# board.net
KiCad netlist of a schematic drawn in EAGLE
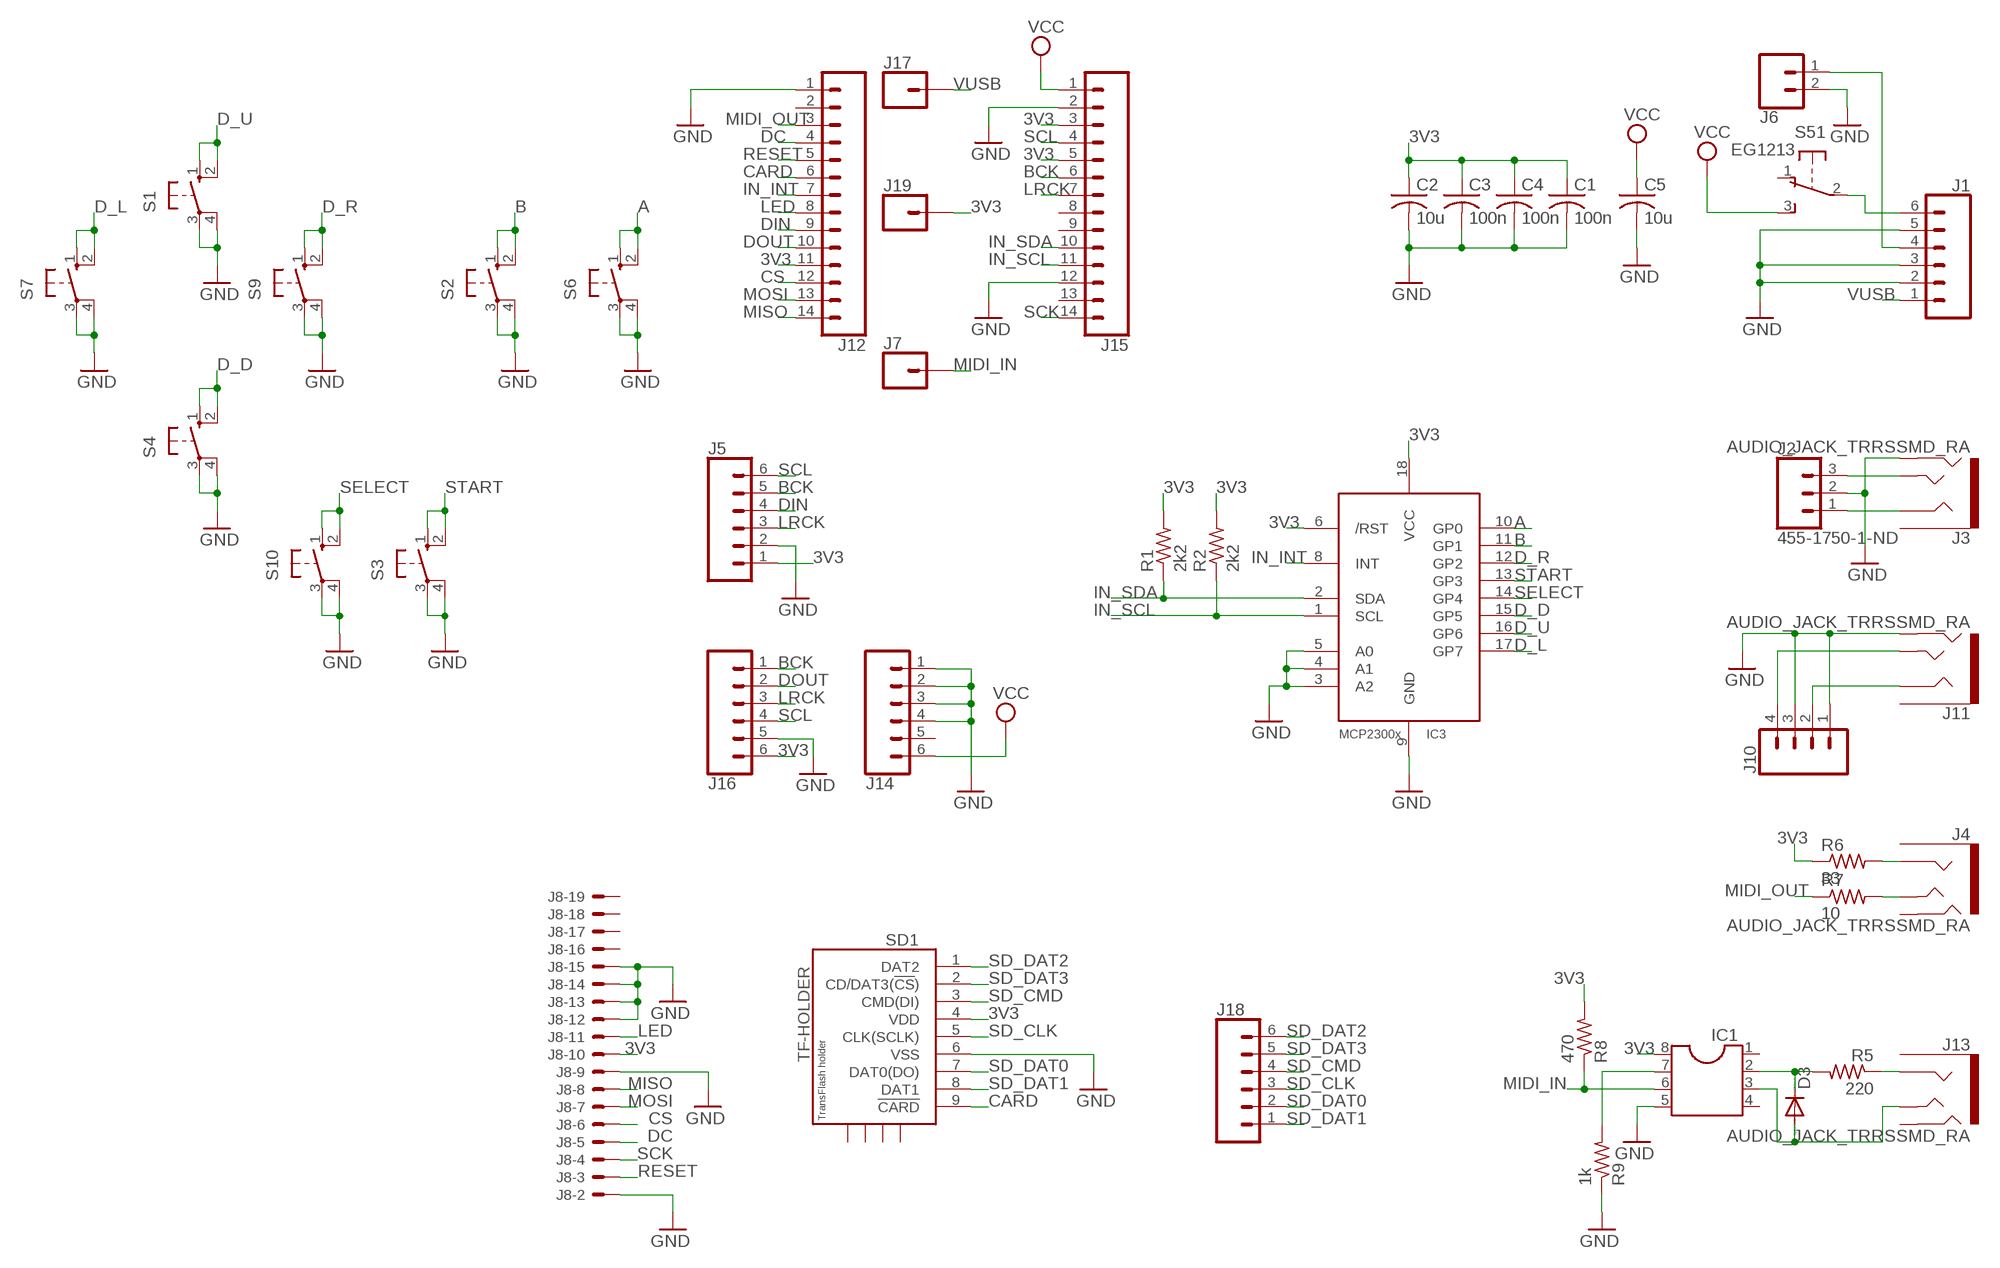
[diagram p0: schematic, sheet 1]

(export (version "E")
  (design (tool "Eeschema 10.0.6"))
  (components
    (comp (ref "C1")
      (value "100n")
      (footprint "eagle-import:C0805")
      (libsource (lib "eagle-import") (part "C-USC0805"))
    )
    (comp (ref "C2")
      (value "10u")
      (footprint "eagle-import:C0805")
      (libsource (lib "eagle-import") (part "C-USC0805"))
    )
    (comp (ref "C3")
      (value "100n")
      (footprint "eagle-import:C0805")
      (libsource (lib "eagle-import") (part "C-USC0805"))
    )
    (comp (ref "C4")
      (value "100n")
      (footprint "eagle-import:C0805")
      (libsource (lib "eagle-import") (part "C-USC0805"))
    )
    (comp (ref "C5")
      (value "10u")
      (footprint "eagle-import:C0805")
      (libsource (lib "eagle-import") (part "C-USC0805"))
    )
    (comp (ref "D3")
      (value "DIODE-MINIMELF")
      (footprint "eagle-import:MINIMELF")
      (libsource (lib "eagle-import") (part "DIODE-MINIMELF"))
    )
    (comp (ref "IC1")
      (value "DIL8")
      (footprint "eagle-import:DIL08")
      (libsource (lib "eagle-import") (part "DIL8"))
    )
    (comp (ref "IC3")
      (value "MCP23008/SO")
      (footprint "eagle-import:SO18W")
      (libsource (lib "eagle-import") (part "MCP23008/SO"))
    )
    (comp (ref "J1")
      (value "CONN_06SILK_FEMALE_PTH")
      (footprint "eagle-import:1X06")
      (libsource (lib "eagle-import") (part "CONN_06SILK_FEMALE_PTH"))
    )
    (comp (ref "J2")
      (value "455-1750-1-ND")
      (footprint "eagle-import:1X03")
      (libsource (lib "eagle-import") (part "CONN_03"))
    )
    (comp (ref "J3")
      (value "AUDIO_JACK_TRRSSMD_RA")
      (footprint "eagle-import:AUDIO_JACK_3.5MM_TRRS_SMD_RA")
      (libsource (lib "eagle-import") (part "AUDIO_JACK_TRRSSMD_RA"))
    )
    (comp (ref "J4")
      (value "AUDIO_JACK_TRRSSMD_RA")
      (footprint "eagle-import:AUDIO_JACK_3.5MM_TRRS_SMD_RA")
      (libsource (lib "eagle-import") (part "AUDIO_JACK_TRRSSMD_RA"))
    )
    (comp (ref "J5")
      (value "CONN_06SILK_FEMALE_PTH")
      (footprint "eagle-import:1X06")
      (libsource (lib "eagle-import") (part "CONN_06SILK_FEMALE_PTH"))
    )
    (comp (ref "J6")
      (value "CONN_02")
      (footprint "eagle-import:1X02")
      (libsource (lib "eagle-import") (part "CONN_02"))
    )
    (comp (ref "J7")
      (value "CONN_01")
      (footprint "eagle-import:1X01")
      (libsource (lib "eagle-import") (part "CONN_01"))
    )
    (comp (ref "J8")
      (value "XF2E-2015-1")
      (footprint "eagle-import:XF2E-2015-1")
      (libsource (lib "eagle-import") (part "XF2-20?15-1E"))
    )
    (comp (ref "J10")
      (value "CONN_04")
      (footprint "eagle-import:1X04")
      (libsource (lib "eagle-import") (part "CONN_04"))
    )
    (comp (ref "J11")
      (value "AUDIO_JACK_TRRSSMD_RA")
      (footprint "eagle-import:AUDIO_JACK_3.5MM_TRRS_SMD_RA")
      (libsource (lib "eagle-import") (part "AUDIO_JACK_TRRSSMD_RA"))
    )
    (comp (ref "J12")
      (value "CONN_14")
      (footprint "eagle-import:1X14")
      (libsource (lib "eagle-import") (part "CONN_14"))
    )
    (comp (ref "J13")
      (value "AUDIO_JACK_TRRSSMD_RA")
      (footprint "eagle-import:AUDIO_JACK_3.5MM_TRRS_SMD_RA")
      (libsource (lib "eagle-import") (part "AUDIO_JACK_TRRSSMD_RA"))
    )
    (comp (ref "J14")
      (value "CONN_06SILK_FEMALE_PTH")
      (footprint "eagle-import:1X06")
      (libsource (lib "eagle-import") (part "CONN_06SILK_FEMALE_PTH"))
    )
    (comp (ref "J15")
      (value "CONN_14")
      (footprint "eagle-import:1X14")
      (libsource (lib "eagle-import") (part "CONN_14"))
    )
    (comp (ref "J16")
      (value "CONN_06SILK_FEMALE_PTH")
      (footprint "eagle-import:1X06")
      (libsource (lib "eagle-import") (part "CONN_06SILK_FEMALE_PTH"))
    )
    (comp (ref "J17")
      (value "CONN_01")
      (footprint "eagle-import:1X01")
      (libsource (lib "eagle-import") (part "CONN_01"))
    )
    (comp (ref "J18")
      (value "CONN_06SILK_FEMALE_PTH")
      (footprint "eagle-import:1X06")
      (libsource (lib "eagle-import") (part "CONN_06SILK_FEMALE_PTH"))
    )
    (comp (ref "J19")
      (value "CONN_01")
      (footprint "eagle-import:1X01")
      (libsource (lib "eagle-import") (part "CONN_01"))
    )
    (comp (ref "R1")
      (value "2k2")
      (footprint "eagle-import:R0805")
      (libsource (lib "eagle-import") (part "R-US_R0805"))
    )
    (comp (ref "R2")
      (value "2k2")
      (footprint "eagle-import:R0805")
      (libsource (lib "eagle-import") (part "R-US_R0805"))
    )
    (comp (ref "R5")
      (value "220")
      (footprint "eagle-import:R0805")
      (libsource (lib "eagle-import") (part "R-US_R0805"))
    )
    (comp (ref "R6")
      (value "33")
      (footprint "eagle-import:R0805")
      (libsource (lib "eagle-import") (part "R-US_R0805"))
    )
    (comp (ref "R7")
      (value "10")
      (footprint "eagle-import:R0805")
      (libsource (lib "eagle-import") (part "R-US_R0805"))
    )
    (comp (ref "R8")
      (value "470")
      (footprint "eagle-import:R0805")
      (libsource (lib "eagle-import") (part "R-US_R0805"))
    )
    (comp (ref "R9")
      (value "1k")
      (footprint "eagle-import:R0805")
      (libsource (lib "eagle-import") (part "R-US_R0805"))
    )
    (comp (ref "S1")
      (value "10-XX")
      (footprint "eagle-import:B3F-10XX")
      (fields (field (name "MPN") "B3F-1000"))
      (libsource (lib "eagle-import") (part "10-XX"))
    )
    (comp (ref "S2")
      (value "10-XX")
      (footprint "eagle-import:B3F-10XX")
      (fields (field (name "MPN") "B3F-1000"))
      (libsource (lib "eagle-import") (part "10-XX"))
    )
    (comp (ref "S3")
      (value "10-XX")
      (footprint "eagle-import:B3F-10XX")
      (fields (field (name "MPN") "B3F-1000"))
      (libsource (lib "eagle-import") (part "10-XX"))
    )
    (comp (ref "S4")
      (value "10-XX")
      (footprint "eagle-import:B3F-10XX")
      (fields (field (name "MPN") "B3F-1000"))
      (libsource (lib "eagle-import") (part "10-XX"))
    )
    (comp (ref "S5")
      (value "EG1213")
      (footprint "eagle-import:EG1213")
      (libsource (lib "eagle-import") (part "EG1213"))
    )
    (comp (ref "S6")
      (value "10-XX")
      (footprint "eagle-import:B3F-10XX")
      (fields (field (name "MPN") "B3F-1000"))
      (libsource (lib "eagle-import") (part "10-XX"))
    )
    (comp (ref "S7")
      (value "10-XX")
      (footprint "eagle-import:B3F-10XX")
      (fields (field (name "MPN") "B3F-1000"))
      (libsource (lib "eagle-import") (part "10-XX"))
    )
    (comp (ref "S9")
      (value "10-XX")
      (footprint "eagle-import:B3F-10XX")
      (fields (field (name "MPN") "B3F-1000"))
      (libsource (lib "eagle-import") (part "10-XX"))
    )
    (comp (ref "S10")
      (value "10-XX")
      (footprint "eagle-import:B3F-10XX")
      (fields (field (name "MPN") "B3F-1000"))
      (libsource (lib "eagle-import") (part "10-XX"))
    )
    (comp (ref "SD1")
      (value "TF-HOLDER")
      (footprint "eagle-import:TF-PULL")
      (libsource (lib "eagle-import") (part "TF-HOLDER"))
    )
  )
  (nets
    (net (code "1") (name "/3V3") (class "Default")
      (node (ref "C1") (pin "1") (pinfunction "1_1") (pintype "passive"))
      (node (ref "C2") (pin "1") (pinfunction "1_1") (pintype "passive"))
      (node (ref "C3") (pin "1") (pinfunction "1_1") (pintype "passive"))
      (node (ref "C4") (pin "1") (pinfunction "1_1") (pintype "passive"))
      (node (ref "IC1") (pin "8") (pinfunction "8_8") (pintype "passive"))
      (node (ref "IC3") (pin "18") (pinfunction "VCC_18") (pintype "power_in"))
      (node (ref "IC3") (pin "6") (pinfunction "/RST_6") (pintype "input"))
      (node (ref "J12") (pin "11") (pinfunction "11_11") (pintype "passive"))
      (node (ref "J15") (pin "3") (pinfunction "3_3") (pintype "passive"))
      (node (ref "J15") (pin "5") (pinfunction "5_5") (pintype "passive"))
      (node (ref "J16") (pin "6") (pinfunction "6_6") (pintype "passive"))
      (node (ref "J19") (pin "1") (pinfunction "1_1") (pintype "passive"))
      (node (ref "J5") (pin "1") (pinfunction "1_1") (pintype "passive"))
      (node (ref "J8") (pin "10") (pinfunction "MS_10") (pintype "passive"))
      (node (ref "R1") (pin "2") (pinfunction "2_2") (pintype "passive"))
      (node (ref "R2") (pin "2") (pinfunction "2_2") (pintype "passive"))
      (node (ref "R6") (pin "1") (pinfunction "1_1") (pintype "passive"))
      (node (ref "R8") (pin "2") (pinfunction "2_2") (pintype "passive"))
      (node (ref "SD1") (pin "4") (pinfunction "VDD_4") (pintype "power_in"))
    )
    (net (code "2") (name "/A") (class "Default")
      (node (ref "IC3") (pin "10") (pinfunction "GP0_10") (pintype "bidirectional"))
      (node (ref "S6") (pin "1") (pinfunction "S_1") (pintype "passive"))
      (node (ref "S6") (pin "2") (pinfunction "S1_2") (pintype "passive"))
    )
    (net (code "3") (name "/B") (class "Default")
      (node (ref "IC3") (pin "11") (pinfunction "GP1_11") (pintype "bidirectional"))
      (node (ref "S2") (pin "1") (pinfunction "S_1") (pintype "passive"))
      (node (ref "S2") (pin "2") (pinfunction "S1_2") (pintype "passive"))
    )
    (net (code "4") (name "/BCK") (class "Default")
      (node (ref "J15") (pin "6") (pinfunction "6_6") (pintype "passive"))
      (node (ref "J16") (pin "1") (pinfunction "1_1") (pintype "passive"))
      (node (ref "J5") (pin "5") (pinfunction "5_5") (pintype "passive"))
    )
    (net (code "5") (name "/CARD") (class "Default")
      (node (ref "J12") (pin "6") (pinfunction "6_6") (pintype "passive"))
      (node (ref "SD1") (pin "9") (pinfunction "~{CARD}_9") (pintype "passive"))
    )
    (net (code "6") (name "/CS") (class "Default")
      (node (ref "J12") (pin "12") (pinfunction "12_12") (pintype "passive"))
      (node (ref "J8") (pin "6") (pinfunction "MS_6") (pintype "passive"))
    )
    (net (code "7") (name "/DC") (class "Default")
      (node (ref "J12") (pin "4") (pinfunction "4_4") (pintype "passive"))
      (node (ref "J8") (pin "5") (pinfunction "MS_5") (pintype "passive"))
    )
    (net (code "8") (name "/DIN") (class "Default")
      (node (ref "J12") (pin "9") (pinfunction "9_9") (pintype "passive"))
      (node (ref "J5") (pin "4") (pinfunction "4_4") (pintype "passive"))
    )
    (net (code "9") (name "/DOUT") (class "Default")
      (node (ref "J12") (pin "10") (pinfunction "10_10") (pintype "passive"))
      (node (ref "J16") (pin "2") (pinfunction "2_2") (pintype "passive"))
    )
    (net (code "10") (name "/D_D") (class "Default")
      (node (ref "IC3") (pin "15") (pinfunction "GP5_15") (pintype "bidirectional"))
      (node (ref "S4") (pin "1") (pinfunction "S_1") (pintype "passive"))
      (node (ref "S4") (pin "2") (pinfunction "S1_2") (pintype "passive"))
    )
    (net (code "11") (name "/D_L") (class "Default")
      (node (ref "IC3") (pin "17") (pinfunction "GP7_17") (pintype "bidirectional"))
      (node (ref "S7") (pin "1") (pinfunction "S_1") (pintype "passive"))
      (node (ref "S7") (pin "2") (pinfunction "S1_2") (pintype "passive"))
    )
    (net (code "12") (name "/D_R") (class "Default")
      (node (ref "IC3") (pin "12") (pinfunction "GP2_12") (pintype "bidirectional"))
      (node (ref "S9") (pin "1") (pinfunction "S_1") (pintype "passive"))
      (node (ref "S9") (pin "2") (pinfunction "S1_2") (pintype "passive"))
    )
    (net (code "13") (name "/D_U") (class "Default")
      (node (ref "IC3") (pin "16") (pinfunction "GP6_16") (pintype "bidirectional"))
      (node (ref "S1") (pin "1") (pinfunction "S_1") (pintype "passive"))
      (node (ref "S1") (pin "2") (pinfunction "S1_2") (pintype "passive"))
    )
    (net (code "14") (name "/IN_INT") (class "Default")
      (node (ref "IC3") (pin "8") (pinfunction "INT_8") (pintype "output"))
      (node (ref "J12") (pin "7") (pinfunction "7_7") (pintype "passive"))
    )
    (net (code "15") (name "/IN_SCL") (class "Default")
      (node (ref "IC3") (pin "1") (pinfunction "SCL_1") (pintype "bidirectional"))
      (node (ref "J15") (pin "11") (pinfunction "11_11") (pintype "passive"))
      (node (ref "R2") (pin "1") (pinfunction "1_1") (pintype "passive"))
    )
    (net (code "16") (name "/IN_SDA") (class "Default")
      (node (ref "IC3") (pin "2") (pinfunction "SDA_2") (pintype "bidirectional"))
      (node (ref "J15") (pin "10") (pinfunction "10_10") (pintype "passive"))
      (node (ref "R1") (pin "1") (pinfunction "1_1") (pintype "passive"))
    )
    (net (code "17") (name "/LED") (class "Default")
      (node (ref "J12") (pin "8") (pinfunction "8_8") (pintype "passive"))
      (node (ref "J8") (pin "11") (pinfunction "MS_11") (pintype "passive"))
    )
    (net (code "18") (name "/LRCK") (class "Default")
      (node (ref "J15") (pin "7") (pinfunction "7_7") (pintype "passive"))
      (node (ref "J16") (pin "3") (pinfunction "3_3") (pintype "passive"))
      (node (ref "J5") (pin "3") (pinfunction "3_3") (pintype "passive"))
    )
    (net (code "19") (name "/MIDI_IN") (class "Default")
      (node (ref "IC1") (pin "6") (pinfunction "6_6") (pintype "passive"))
      (node (ref "J7") (pin "1") (pinfunction "1_1") (pintype "passive"))
      (node (ref "R8") (pin "1") (pinfunction "1_1") (pintype "passive"))
    )
    (net (code "20") (name "/MIDI_OUT") (class "Default")
      (node (ref "J12") (pin "3") (pinfunction "3_3") (pintype "passive"))
      (node (ref "R7") (pin "1") (pinfunction "1_1") (pintype "passive"))
    )
    (net (code "21") (name "/MISO") (class "Default")
      (node (ref "J12") (pin "14") (pinfunction "14_14") (pintype "passive"))
      (node (ref "J8") (pin "8") (pinfunction "MS_8") (pintype "passive"))
    )
    (net (code "22") (name "/MOSI") (class "Default")
      (node (ref "J12") (pin "13") (pinfunction "13_13") (pintype "passive"))
      (node (ref "J8") (pin "7") (pinfunction "MS_7") (pintype "passive"))
    )
    (net (code "23") (name "/RESET") (class "Default")
      (node (ref "J12") (pin "5") (pinfunction "5_5") (pintype "passive"))
      (node (ref "J8") (pin "3") (pinfunction "MS_3") (pintype "passive"))
    )
    (net (code "24") (name "/SCK") (class "Default")
      (node (ref "J15") (pin "14") (pinfunction "14_14") (pintype "passive"))
      (node (ref "J8") (pin "4") (pinfunction "MS_4") (pintype "passive"))
    )
    (net (code "25") (name "/SCL") (class "Default")
      (node (ref "J15") (pin "4") (pinfunction "4_4") (pintype "passive"))
      (node (ref "J16") (pin "4") (pinfunction "4_4") (pintype "passive"))
      (node (ref "J5") (pin "6") (pinfunction "6_6") (pintype "passive"))
    )
    (net (code "26") (name "/SD_CLK") (class "Default")
      (node (ref "J18") (pin "3") (pinfunction "3_3") (pintype "passive"))
      (node (ref "SD1") (pin "5") (pinfunction "CLK(SCLK)_5") (pintype "input"))
    )
    (net (code "27") (name "/SD_CMD") (class "Default")
      (node (ref "J18") (pin "4") (pinfunction "4_4") (pintype "passive"))
      (node (ref "SD1") (pin "3") (pinfunction "CMD(DI)_3") (pintype "bidirectional"))
    )
    (net (code "28") (name "/SD_DAT0") (class "Default")
      (node (ref "J18") (pin "2") (pinfunction "2_2") (pintype "passive"))
      (node (ref "SD1") (pin "7") (pinfunction "DAT0(DO)_7") (pintype "bidirectional"))
    )
    (net (code "29") (name "/SD_DAT1") (class "Default")
      (node (ref "J18") (pin "1") (pinfunction "1_1") (pintype "passive"))
      (node (ref "SD1") (pin "8") (pinfunction "DAT1_8") (pintype "bidirectional"))
    )
    (net (code "30") (name "/SD_DAT2") (class "Default")
      (node (ref "J18") (pin "6") (pinfunction "6_6") (pintype "passive"))
      (node (ref "SD1") (pin "1") (pinfunction "DAT2_1") (pintype "bidirectional"))
    )
    (net (code "31") (name "/SD_DAT3") (class "Default")
      (node (ref "J18") (pin "5") (pinfunction "5_5") (pintype "passive"))
      (node (ref "SD1") (pin "2") (pinfunction "CD/DAT3(~{CS})_2") (pintype "bidirectional"))
    )
    (net (code "32") (name "/SELECT") (class "Default")
      (node (ref "IC3") (pin "14") (pinfunction "GP4_14") (pintype "bidirectional"))
      (node (ref "S10") (pin "1") (pinfunction "S_1") (pintype "passive"))
      (node (ref "S10") (pin "2") (pinfunction "S1_2") (pintype "passive"))
    )
    (net (code "33") (name "/START") (class "Default")
      (node (ref "IC3") (pin "13") (pinfunction "GP3_13") (pintype "bidirectional"))
      (node (ref "S3") (pin "1") (pinfunction "S_1") (pintype "passive"))
      (node (ref "S3") (pin "2") (pinfunction "S1_2") (pintype "passive"))
    )
    (net (code "34") (name "/VUSB") (class "Default")
      (node (ref "J1") (pin "1") (pinfunction "1_1") (pintype "passive"))
      (node (ref "J17") (pin "1") (pinfunction "1_1") (pintype "passive"))
    )
    (net (code "35") (name "GND") (class "Default")
      (node (ref "C1") (pin "2") (pinfunction "2_2") (pintype "passive"))
      (node (ref "C2") (pin "2") (pinfunction "2_2") (pintype "passive"))
      (node (ref "C3") (pin "2") (pinfunction "2_2") (pintype "passive"))
      (node (ref "C4") (pin "2") (pinfunction "2_2") (pintype "passive"))
      (node (ref "C5") (pin "2") (pinfunction "2_2") (pintype "passive"))
      (node (ref "IC1") (pin "5") (pinfunction "5_5") (pintype "passive"))
      (node (ref "IC3") (pin "3") (pinfunction "A2_3") (pintype "input"))
      (node (ref "IC3") (pin "4") (pinfunction "A1_4") (pintype "input"))
      (node (ref "IC3") (pin "5") (pinfunction "A0_5") (pintype "input"))
      (node (ref "IC3") (pin "9") (pinfunction "GND_9") (pintype "power_in"))
      (node (ref "J1") (pin "2") (pinfunction "2_2") (pintype "passive"))
      (node (ref "J1") (pin "3") (pinfunction "3_3") (pintype "passive"))
      (node (ref "J1") (pin "5") (pinfunction "5_5") (pintype "passive"))
      (node (ref "J10") (pin "1") (pinfunction "1_1") (pintype "passive"))
      (node (ref "J10") (pin "3") (pinfunction "3_3") (pintype "passive"))
      (node (ref "J11") (pin "RING2") (pinfunction "RING2_RING2") (pintype "bidirectional"))
      (node (ref "J12") (pin "1") (pinfunction "1_1") (pintype "passive"))
      (node (ref "J14") (pin "1") (pinfunction "1_1") (pintype "passive"))
      (node (ref "J14") (pin "2") (pinfunction "2_2") (pintype "passive"))
      (node (ref "J14") (pin "3") (pinfunction "3_3") (pintype "passive"))
      (node (ref "J14") (pin "4") (pinfunction "4_4") (pintype "passive"))
      (node (ref "J15") (pin "12") (pinfunction "12_12") (pintype "passive"))
      (node (ref "J15") (pin "2") (pinfunction "2_2") (pintype "passive"))
      (node (ref "J16") (pin "5") (pinfunction "5_5") (pintype "passive"))
      (node (ref "J2") (pin "2") (pinfunction "2_2") (pintype "passive"))
      (node (ref "J3") (pin "RING2") (pinfunction "RING2_RING2") (pintype "bidirectional"))
      (node (ref "J5") (pin "2") (pinfunction "2_2") (pintype "passive"))
      (node (ref "J6") (pin "2") (pinfunction "2_2") (pintype "passive"))
      (node (ref "J8") (pin "12") (pinfunction "MS_12") (pintype "passive"))
      (node (ref "J8") (pin "13") (pinfunction "MS_13") (pintype "passive"))
      (node (ref "J8") (pin "14") (pinfunction "MS_14") (pintype "passive"))
      (node (ref "J8") (pin "15") (pinfunction "MS_15") (pintype "passive"))
      (node (ref "J8") (pin "2") (pinfunction "MS_2") (pintype "passive"))
      (node (ref "J8") (pin "9") (pinfunction "MS_9") (pintype "passive"))
      (node (ref "R9") (pin "1") (pinfunction "1_1") (pintype "passive"))
      (node (ref "S1") (pin "3") (pinfunction "P_3") (pintype "passive"))
      (node (ref "S1") (pin "4") (pinfunction "P1_4") (pintype "passive"))
      (node (ref "S10") (pin "3") (pinfunction "P_3") (pintype "passive"))
      (node (ref "S10") (pin "4") (pinfunction "P1_4") (pintype "passive"))
      (node (ref "S2") (pin "3") (pinfunction "P_3") (pintype "passive"))
      (node (ref "S2") (pin "4") (pinfunction "P1_4") (pintype "passive"))
      (node (ref "S3") (pin "3") (pinfunction "P_3") (pintype "passive"))
      (node (ref "S3") (pin "4") (pinfunction "P1_4") (pintype "passive"))
      (node (ref "S4") (pin "3") (pinfunction "P_3") (pintype "passive"))
      (node (ref "S4") (pin "4") (pinfunction "P1_4") (pintype "passive"))
      (node (ref "S6") (pin "3") (pinfunction "P_3") (pintype "passive"))
      (node (ref "S6") (pin "4") (pinfunction "P1_4") (pintype "passive"))
      (node (ref "S7") (pin "3") (pinfunction "P_3") (pintype "passive"))
      (node (ref "S7") (pin "4") (pinfunction "P1_4") (pintype "passive"))
      (node (ref "S9") (pin "3") (pinfunction "P_3") (pintype "passive"))
      (node (ref "S9") (pin "4") (pinfunction "P1_4") (pintype "passive"))
      (node (ref "SD1") (pin "6") (pinfunction "VSS_6") (pintype "power_in"))
    )
    (net (code "36") (name "Net-(D3-PadA)") (class "Default")
      (node (ref "D3") (pin "A") (pinfunction "A_A") (pintype "passive"))
      (node (ref "IC1") (pin "3") (pinfunction "3_3") (pintype "passive"))
      (node (ref "J13") (pin "TIP") (pinfunction "TIP_TIP") (pintype "bidirectional"))
    )
    (net (code "37") (name "Net-(D3-PadC)") (class "Default")
      (node (ref "D3") (pin "C") (pinfunction "C_C") (pintype "passive"))
      (node (ref "IC1") (pin "2") (pinfunction "2_2") (pintype "passive"))
      (node (ref "R5") (pin "2") (pinfunction "2_2") (pintype "passive"))
    )
    (net (code "38") (name "Net-(IC1-Pad7)") (class "Default")
      (node (ref "IC1") (pin "7") (pinfunction "7_7") (pintype "passive"))
      (node (ref "R9") (pin "2") (pinfunction "2_2") (pintype "passive"))
    )
    (net (code "39") (name "Net-(J1-Pad4)") (class "Default")
      (node (ref "J1") (pin "4") (pinfunction "4_4") (pintype "passive"))
      (node (ref "J6") (pin "1") (pinfunction "1_1") (pintype "passive"))
    )
    (net (code "40") (name "Net-(J2-Pad1)") (class "Default")
      (node (ref "J2") (pin "1") (pinfunction "1_1") (pintype "passive"))
      (node (ref "J3") (pin "RING1") (pinfunction "RING1_RING1") (pintype "bidirectional"))
    )
    (net (code "41") (name "Net-(J2-Pad3)") (class "Default")
      (node (ref "J2") (pin "3") (pinfunction "3_3") (pintype "passive"))
      (node (ref "J3") (pin "TIP") (pinfunction "TIP_TIP") (pintype "bidirectional"))
    )
    (net (code "42") (name "Net-(J4-PadRING1)") (class "Default")
      (node (ref "J4") (pin "RING1") (pinfunction "RING1_RING1") (pintype "bidirectional"))
      (node (ref "R6") (pin "2") (pinfunction "2_2") (pintype "passive"))
    )
    (net (code "43") (name "Net-(J4-PadTIP)") (class "Default")
      (node (ref "J4") (pin "TIP") (pinfunction "TIP_TIP") (pintype "bidirectional"))
      (node (ref "R7") (pin "2") (pinfunction "2_2") (pintype "passive"))
    )
    (net (code "44") (name "Net-(J10-Pad2)") (class "Default")
      (node (ref "J10") (pin "2") (pinfunction "2_2") (pintype "passive"))
      (node (ref "J11") (pin "RING1") (pinfunction "RING1_RING1") (pintype "bidirectional"))
    )
    (net (code "45") (name "Net-(J10-Pad4)") (class "Default")
      (node (ref "J10") (pin "4") (pinfunction "4_4") (pintype "passive"))
      (node (ref "J11") (pin "TIP") (pinfunction "TIP_TIP") (pintype "bidirectional"))
    )
    (net (code "46") (name "Net-(J13-PadRING1)") (class "Default")
      (node (ref "J13") (pin "RING1") (pinfunction "RING1_RING1") (pintype "bidirectional"))
      (node (ref "R5") (pin "1") (pinfunction "1_1") (pintype "passive"))
    )
    (net (code "47") (name "Net-(S5A-P)") (class "Default")
      (node (ref "J1") (pin "6") (pinfunction "6_6") (pintype "passive"))
      (node (ref "S5") (pin "2") (pinfunction "P_2") (pintype "passive"))
    )
    (net (code "48") (name "VCC") (class "Default")
      (node (ref "C5") (pin "1") (pinfunction "1_1") (pintype "passive"))
      (node (ref "J14") (pin "6") (pinfunction "6_6") (pintype "passive"))
      (node (ref "J15") (pin "1") (pinfunction "1_1") (pintype "passive"))
      (node (ref "S5") (pin "3") (pinfunction "S_3") (pintype "passive"))
    )
    (net (code "49") (name "unconnected-(IC1-Pad1)") (class "Default")
      (node (ref "IC1") (pin "1") (pinfunction "1_1") (pintype "passive"))
    )
    (net (code "50") (name "unconnected-(IC1-Pad4)") (class "Default")
      (node (ref "IC1") (pin "4") (pinfunction "4_4") (pintype "passive"))
    )
    (net (code "51") (name "unconnected-(J3-PadEARTH)") (class "Default")
      (node (ref "J3") (pin "EARTH") (pinfunction "EARTH_EARTH") (pintype "bidirectional"))
    )
    (net (code "52") (name "unconnected-(J4-PadEARTH)") (class "Default")
      (node (ref "J4") (pin "EARTH") (pinfunction "EARTH_EARTH") (pintype "bidirectional"))
    )
    (net (code "53") (name "unconnected-(J4-PadRING2)") (class "Default")
      (node (ref "J4") (pin "RING2") (pinfunction "RING2_RING2") (pintype "bidirectional"))
    )
    (net (code "54") (name "unconnected-(J8G-MS-Pad16)") (class "Default")
      (node (ref "J8") (pin "16") (pinfunction "MS_16") (pintype "passive"))
    )
    (net (code "55") (name "unconnected-(J8H-MS-Pad17)") (class "Default")
      (node (ref "J8") (pin "17") (pinfunction "MS_17") (pintype "passive"))
    )
    (net (code "56") (name "unconnected-(J8I-MS-Pad18)") (class "Default")
      (node (ref "J8") (pin "18") (pinfunction "MS_18") (pintype "passive"))
    )
    (net (code "57") (name "unconnected-(J8J-MS-Pad19)") (class "Default")
      (node (ref "J8") (pin "19") (pinfunction "MS_19") (pintype "passive"))
    )
    (net (code "58") (name "unconnected-(J11-PadEARTH)") (class "Default")
      (node (ref "J11") (pin "EARTH") (pinfunction "EARTH_EARTH") (pintype "bidirectional"))
    )
    (net (code "59") (name "unconnected-(J12-Pad2)") (class "Default")
      (node (ref "J12") (pin "2") (pinfunction "2_2") (pintype "passive"))
    )
    (net (code "60") (name "unconnected-(J13-PadEARTH)") (class "Default")
      (node (ref "J13") (pin "EARTH") (pinfunction "EARTH_EARTH") (pintype "bidirectional"))
    )
    (net (code "61") (name "unconnected-(J13-PadRING2)") (class "Default")
      (node (ref "J13") (pin "RING2") (pinfunction "RING2_RING2") (pintype "bidirectional"))
    )
    (net (code "62") (name "unconnected-(J14-Pad5)") (class "Default")
      (node (ref "J14") (pin "5") (pinfunction "5_5") (pintype "passive"))
    )
    (net (code "63") (name "unconnected-(J15-Pad8)") (class "Default")
      (node (ref "J15") (pin "8") (pinfunction "8_8") (pintype "passive"))
    )
    (net (code "64") (name "unconnected-(J15-Pad9)") (class "Default")
      (node (ref "J15") (pin "9") (pinfunction "9_9") (pintype "passive"))
    )
    (net (code "65") (name "unconnected-(J15-Pad13)") (class "Default")
      (node (ref "J15") (pin "13") (pinfunction "13_13") (pintype "passive"))
    )
    (net (code "66") (name "unconnected-(S5A-O-Pad1)") (class "Default")
      (node (ref "S5") (pin "1") (pinfunction "O_1") (pintype "passive"))
    )
    (net (code "67") (name "unconnected-(SD1-PadS1)") (class "Default")
      (node (ref "SD1") (pin "S1") (pinfunction "S1_S1") (pintype "passive"))
    )
    (net (code "68") (name "unconnected-(SD1-PadS2)") (class "Default")
      (node (ref "SD1") (pin "S2") (pinfunction "S2_S2") (pintype "passive"))
    )
    (net (code "69") (name "unconnected-(SD1-PadS3)") (class "Default")
      (node (ref "SD1") (pin "S3") (pinfunction "S3_S3") (pintype "passive"))
    )
    (net (code "70") (name "unconnected-(SD1-PadS4)") (class "Default")
      (node (ref "SD1") (pin "S4") (pinfunction "S4_S4") (pintype "passive"))
    )
  )
)
